# AnalogOutLevelShifter.net
KiCad netlist of a schematic drawn in Altium Designer
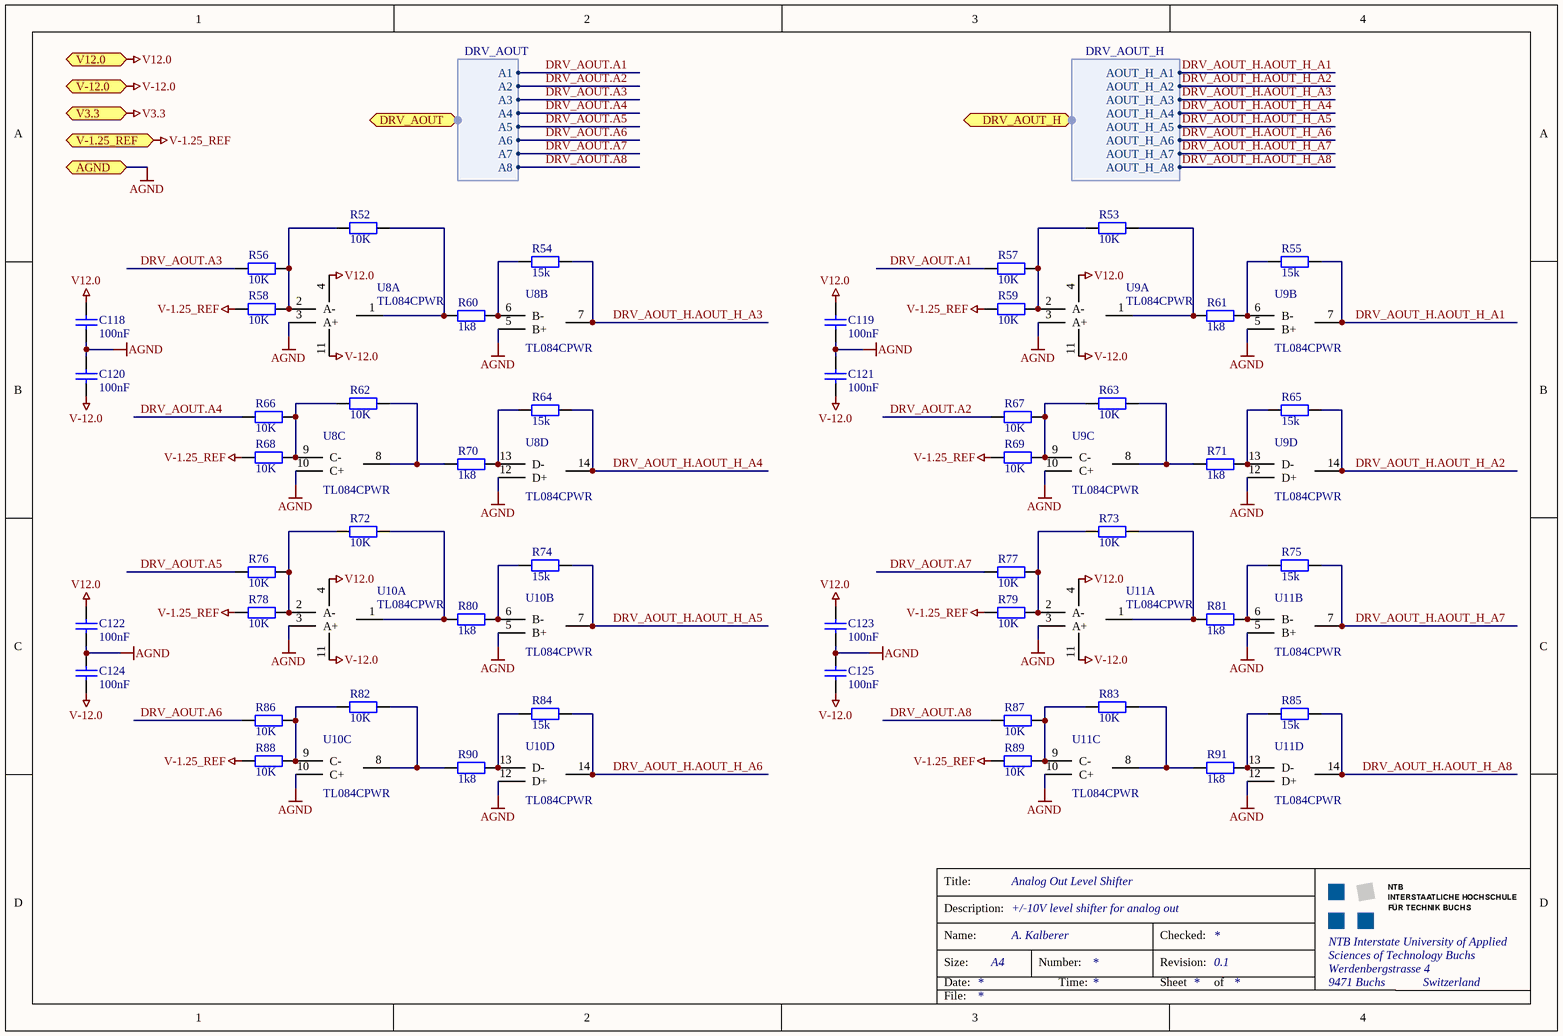
[diagram p0: AnalogOutLevelShifter.SchDoc]

(export (version "E")
  (design (tool "Eeschema 10.0.6"))
  (components
    (comp (ref "C118")
      (value "100nF")
      (footprint "0603_3D")
      (description "Capacitor")
      (fields (field (name "#PUBLISHER") "Dr. A. Heinzelmann"))
      (libsource (lib "ELE-LIB") (part "C"))
    )
    (comp (ref "C119")
      (value "100nF")
      (footprint "0603_3D")
      (description "Capacitor")
      (fields (field (name "#PUBLISHER") "Dr. A. Heinzelmann"))
      (libsource (lib "ELE-LIB") (part "C"))
    )
    (comp (ref "C120")
      (value "100nF")
      (footprint "0603_3D")
      (description "Capacitor")
      (fields (field (name "#PUBLISHER") "Dr. A. Heinzelmann"))
      (libsource (lib "ELE-LIB") (part "C"))
    )
    (comp (ref "C121")
      (value "100nF")
      (footprint "0603_3D")
      (description "Capacitor")
      (fields (field (name "#PUBLISHER") "Dr. A. Heinzelmann"))
      (libsource (lib "ELE-LIB") (part "C"))
    )
    (comp (ref "C122")
      (value "100nF")
      (footprint "0603_3D")
      (description "Capacitor")
      (fields (field (name "#PUBLISHER") "Dr. A. Heinzelmann"))
      (libsource (lib "ELE-LIB") (part "C"))
    )
    (comp (ref "C123")
      (value "100nF")
      (footprint "0603_3D")
      (description "Capacitor")
      (fields (field (name "#PUBLISHER") "Dr. A. Heinzelmann"))
      (libsource (lib "ELE-LIB") (part "C"))
    )
    (comp (ref "C124")
      (value "100nF")
      (footprint "0603_3D")
      (description "Capacitor")
      (fields (field (name "#PUBLISHER") "Dr. A. Heinzelmann"))
      (libsource (lib "ELE-LIB") (part "C"))
    )
    (comp (ref "C125")
      (value "100nF")
      (footprint "0603_3D")
      (description "Capacitor")
      (fields (field (name "#PUBLISHER") "Dr. A. Heinzelmann"))
      (libsource (lib "ELE-LIB") (part "C"))
    )
    (comp (ref "R52")
      (value "10K")
      (footprint "0603_3D")
      (description "Resistor")
      (fields (field (name "#PUBLISHER") "Dr. A. Heinzelmann"))
      (libsource (lib "PartLib") (part "R"))
    )
    (comp (ref "R53")
      (value "10K")
      (footprint "0603_3D")
      (description "Resistor")
      (fields (field (name "#PUBLISHER") "Dr. A. Heinzelmann"))
      (libsource (lib "PartLib") (part "R"))
    )
    (comp (ref "R54")
      (value "15k")
      (footprint "0603_3D")
      (description "Resistor")
      (fields (field (name "#PUBLISHER") "Dr. A. Heinzelmann"))
      (libsource (lib "PartLib") (part "R"))
    )
    (comp (ref "R55")
      (value "15k")
      (footprint "0603_3D")
      (description "Resistor")
      (fields (field (name "#PUBLISHER") "Dr. A. Heinzelmann"))
      (libsource (lib "PartLib") (part "R"))
    )
    (comp (ref "R56")
      (value "10K")
      (footprint "0603_3D")
      (description "Resistor")
      (fields (field (name "#PUBLISHER") "Dr. A. Heinzelmann"))
      (libsource (lib "PartLib") (part "R"))
    )
    (comp (ref "R57")
      (value "10K")
      (footprint "0603_3D")
      (description "Resistor")
      (fields (field (name "#PUBLISHER") "Dr. A. Heinzelmann"))
      (libsource (lib "PartLib") (part "R"))
    )
    (comp (ref "R58")
      (value "10K")
      (footprint "0603_3D")
      (description "Resistor")
      (fields (field (name "#PUBLISHER") "Dr. A. Heinzelmann"))
      (libsource (lib "PartLib") (part "R"))
    )
    (comp (ref "R59")
      (value "10K")
      (footprint "0603_3D")
      (description "Resistor")
      (fields (field (name "#PUBLISHER") "Dr. A. Heinzelmann"))
      (libsource (lib "PartLib") (part "R"))
    )
    (comp (ref "R60")
      (value "1k8")
      (footprint "0603_3D")
      (description "Resistor")
      (fields (field (name "#PUBLISHER") "Dr. A. Heinzelmann"))
      (libsource (lib "PartLib") (part "R"))
    )
    (comp (ref "R61")
      (value "1k8")
      (footprint "0603_3D")
      (description "Resistor")
      (fields (field (name "#PUBLISHER") "Dr. A. Heinzelmann"))
      (libsource (lib "PartLib") (part "R"))
    )
    (comp (ref "R62")
      (value "10K")
      (footprint "0603_3D")
      (description "Resistor")
      (fields (field (name "#PUBLISHER") "Dr. A. Heinzelmann"))
      (libsource (lib "PartLib") (part "R"))
    )
    (comp (ref "R63")
      (value "10K")
      (footprint "0603_3D")
      (description "Resistor")
      (fields (field (name "#PUBLISHER") "Dr. A. Heinzelmann"))
      (libsource (lib "PartLib") (part "R"))
    )
    (comp (ref "R64")
      (value "15k")
      (footprint "0603_3D")
      (description "Resistor")
      (fields (field (name "#PUBLISHER") "Dr. A. Heinzelmann"))
      (libsource (lib "PartLib") (part "R"))
    )
    (comp (ref "R65")
      (value "15k")
      (footprint "0603_3D")
      (description "Resistor")
      (fields (field (name "#PUBLISHER") "Dr. A. Heinzelmann"))
      (libsource (lib "PartLib") (part "R"))
    )
    (comp (ref "R66")
      (value "10K")
      (footprint "0603_3D")
      (description "Resistor")
      (fields (field (name "#PUBLISHER") "Dr. A. Heinzelmann"))
      (libsource (lib "PartLib") (part "R"))
    )
    (comp (ref "R67")
      (value "10K")
      (footprint "0603_3D")
      (description "Resistor")
      (fields (field (name "#PUBLISHER") "Dr. A. Heinzelmann"))
      (libsource (lib "PartLib") (part "R"))
    )
    (comp (ref "R68")
      (value "10K")
      (footprint "0603_3D")
      (description "Resistor")
      (fields (field (name "#PUBLISHER") "Dr. A. Heinzelmann"))
      (libsource (lib "PartLib") (part "R"))
    )
    (comp (ref "R69")
      (value "10K")
      (footprint "0603_3D")
      (description "Resistor")
      (fields (field (name "#PUBLISHER") "Dr. A. Heinzelmann"))
      (libsource (lib "PartLib") (part "R"))
    )
    (comp (ref "R70")
      (value "1k8")
      (footprint "0603_3D")
      (description "Resistor")
      (fields (field (name "#PUBLISHER") "Dr. A. Heinzelmann"))
      (libsource (lib "PartLib") (part "R"))
    )
    (comp (ref "R71")
      (value "1k8")
      (footprint "0603_3D")
      (description "Resistor")
      (fields (field (name "#PUBLISHER") "Dr. A. Heinzelmann"))
      (libsource (lib "PartLib") (part "R"))
    )
    (comp (ref "R72")
      (value "10K")
      (footprint "0603_3D")
      (description "Resistor")
      (fields (field (name "#PUBLISHER") "Dr. A. Heinzelmann"))
      (libsource (lib "PartLib") (part "R"))
    )
    (comp (ref "R73")
      (value "10K")
      (footprint "0603_3D")
      (description "Resistor")
      (fields (field (name "#PUBLISHER") "Dr. A. Heinzelmann"))
      (libsource (lib "PartLib") (part "R"))
    )
    (comp (ref "R74")
      (value "15k")
      (footprint "0603_3D")
      (description "Resistor")
      (fields (field (name "#PUBLISHER") "Dr. A. Heinzelmann"))
      (libsource (lib "PartLib") (part "R"))
    )
    (comp (ref "R75")
      (value "15k")
      (footprint "0603_3D")
      (description "Resistor")
      (fields (field (name "#PUBLISHER") "Dr. A. Heinzelmann"))
      (libsource (lib "PartLib") (part "R"))
    )
    (comp (ref "R76")
      (value "10K")
      (footprint "0603_3D")
      (description "Resistor")
      (fields (field (name "#PUBLISHER") "Dr. A. Heinzelmann"))
      (libsource (lib "PartLib") (part "R"))
    )
    (comp (ref "R77")
      (value "10K")
      (footprint "0603_3D")
      (description "Resistor")
      (fields (field (name "#PUBLISHER") "Dr. A. Heinzelmann"))
      (libsource (lib "PartLib") (part "R"))
    )
    (comp (ref "R78")
      (value "10K")
      (footprint "0603_3D")
      (description "Resistor")
      (fields (field (name "#PUBLISHER") "Dr. A. Heinzelmann"))
      (libsource (lib "PartLib") (part "R"))
    )
    (comp (ref "R79")
      (value "10K")
      (footprint "0603_3D")
      (description "Resistor")
      (fields (field (name "#PUBLISHER") "Dr. A. Heinzelmann"))
      (libsource (lib "PartLib") (part "R"))
    )
    (comp (ref "R80")
      (value "1k8")
      (footprint "0603_3D")
      (description "Resistor")
      (fields (field (name "#PUBLISHER") "Dr. A. Heinzelmann"))
      (libsource (lib "PartLib") (part "R"))
    )
    (comp (ref "R81")
      (value "1k8")
      (footprint "0603_3D")
      (description "Resistor")
      (fields (field (name "#PUBLISHER") "Dr. A. Heinzelmann"))
      (libsource (lib "PartLib") (part "R"))
    )
    (comp (ref "R82")
      (value "10K")
      (footprint "0603_3D")
      (description "Resistor")
      (fields (field (name "#PUBLISHER") "Dr. A. Heinzelmann"))
      (libsource (lib "PartLib") (part "R"))
    )
    (comp (ref "R83")
      (value "10K")
      (footprint "0603_3D")
      (description "Resistor")
      (fields (field (name "#PUBLISHER") "Dr. A. Heinzelmann"))
      (libsource (lib "PartLib") (part "R"))
    )
    (comp (ref "R84")
      (value "15k")
      (footprint "0603_3D")
      (description "Resistor")
      (fields (field (name "#PUBLISHER") "Dr. A. Heinzelmann"))
      (libsource (lib "PartLib") (part "R"))
    )
    (comp (ref "R85")
      (value "15k")
      (footprint "0603_3D")
      (description "Resistor")
      (fields (field (name "#PUBLISHER") "Dr. A. Heinzelmann"))
      (libsource (lib "PartLib") (part "R"))
    )
    (comp (ref "R86")
      (value "10K")
      (footprint "0603_3D")
      (description "Resistor")
      (fields (field (name "#PUBLISHER") "Dr. A. Heinzelmann"))
      (libsource (lib "PartLib") (part "R"))
    )
    (comp (ref "R87")
      (value "10K")
      (footprint "0603_3D")
      (description "Resistor")
      (fields (field (name "#PUBLISHER") "Dr. A. Heinzelmann"))
      (libsource (lib "PartLib") (part "R"))
    )
    (comp (ref "R88")
      (value "10K")
      (footprint "0603_3D")
      (description "Resistor")
      (fields (field (name "#PUBLISHER") "Dr. A. Heinzelmann"))
      (libsource (lib "PartLib") (part "R"))
    )
    (comp (ref "R89")
      (value "10K")
      (footprint "0603_3D")
      (description "Resistor")
      (fields (field (name "#PUBLISHER") "Dr. A. Heinzelmann"))
      (libsource (lib "PartLib") (part "R"))
    )
    (comp (ref "R90")
      (value "1k8")
      (footprint "0603_3D")
      (description "Resistor")
      (fields (field (name "#PUBLISHER") "Dr. A. Heinzelmann"))
      (libsource (lib "PartLib") (part "R"))
    )
    (comp (ref "R91")
      (value "1k8")
      (footprint "0603_3D")
      (description "Resistor")
      (fields (field (name "#PUBLISHER") "Dr. A. Heinzelmann"))
      (libsource (lib "PartLib") (part "R"))
    )
    (comp (ref "U8")
      (value "TL084CPWR")
      (footprint "TSOP65P640X120-14N")
      (description "Quad OPAmp")
      (libsource (lib "PartLib") (part "TL084CPWR"))
    )
    (comp (ref "U9")
      (value "TL084CPWR")
      (footprint "TSOP65P640X120-14N")
      (description "Quad OPAmp")
      (libsource (lib "PartLib") (part "TL084CPWR"))
    )
    (comp (ref "U10")
      (value "TL084CPWR")
      (footprint "TSOP65P640X120-14N")
      (description "Quad OPAmp")
      (libsource (lib "PartLib") (part "TL084CPWR"))
    )
    (comp (ref "U11")
      (value "TL084CPWR")
      (footprint "TSOP65P640X120-14N")
      (description "Quad OPAmp")
      (libsource (lib "PartLib") (part "TL084CPWR"))
    )
  )
  (nets
    (net (code "3") (name "/DRV_AOUT.A1") (class "Default")
      (node (ref "R57") (pin "1") (pinfunction "1_1") (pintype "passive"))
    )
    (net (code "4") (name "/DRV_AOUT.A2") (class "Default")
      (node (ref "R67") (pin "1") (pinfunction "1_1") (pintype "passive"))
    )
    (net (code "5") (name "/DRV_AOUT.A3") (class "Default")
      (node (ref "R56") (pin "1") (pinfunction "1_1") (pintype "passive"))
    )
    (net (code "6") (name "/DRV_AOUT.A4") (class "Default")
      (node (ref "R66") (pin "1") (pinfunction "1_1") (pintype "passive"))
    )
    (net (code "7") (name "/DRV_AOUT.A5") (class "Default")
      (node (ref "R76") (pin "1") (pinfunction "1_1") (pintype "passive"))
    )
    (net (code "8") (name "/DRV_AOUT.A6") (class "Default")
      (node (ref "R86") (pin "1") (pinfunction "1_1") (pintype "passive"))
    )
    (net (code "9") (name "/DRV_AOUT.A7") (class "Default")
      (node (ref "R77") (pin "1") (pinfunction "1_1") (pintype "passive"))
    )
    (net (code "10") (name "/DRV_AOUT.A8") (class "Default")
      (node (ref "R87") (pin "1") (pinfunction "1_1") (pintype "passive"))
    )
    (net (code "11") (name "/DRV_AOUT_H.AOUT_H_A1") (class "Default")
      (node (ref "R55") (pin "2") (pinfunction "2_2") (pintype "passive"))
      (node (ref "U9") (pin "7") (pinfunction "Bout_7") (pintype "passive"))
    )
    (net (code "12") (name "/DRV_AOUT_H.AOUT_H_A2") (class "Default")
      (node (ref "R65") (pin "2") (pinfunction "2_2") (pintype "passive"))
      (node (ref "U9") (pin "14") (pinfunction "Dout_14") (pintype "passive"))
    )
    (net (code "13") (name "/DRV_AOUT_H.AOUT_H_A3") (class "Default")
      (node (ref "R54") (pin "2") (pinfunction "2_2") (pintype "passive"))
      (node (ref "U8") (pin "7") (pinfunction "Bout_7") (pintype "passive"))
    )
    (net (code "14") (name "/DRV_AOUT_H.AOUT_H_A4") (class "Default")
      (node (ref "R64") (pin "2") (pinfunction "2_2") (pintype "passive"))
      (node (ref "U8") (pin "14") (pinfunction "Dout_14") (pintype "passive"))
    )
    (net (code "15") (name "/DRV_AOUT_H.AOUT_H_A5") (class "Default")
      (node (ref "R74") (pin "2") (pinfunction "2_2") (pintype "passive"))
      (node (ref "U10") (pin "7") (pinfunction "Bout_7") (pintype "passive"))
    )
    (net (code "16") (name "/DRV_AOUT_H.AOUT_H_A6") (class "Default")
      (node (ref "R84") (pin "2") (pinfunction "2_2") (pintype "passive"))
      (node (ref "U10") (pin "14") (pinfunction "Dout_14") (pintype "passive"))
    )
    (net (code "17") (name "/DRV_AOUT_H.AOUT_H_A7") (class "Default")
      (node (ref "R75") (pin "2") (pinfunction "2_2") (pintype "passive"))
      (node (ref "U11") (pin "7") (pinfunction "Bout_7") (pintype "passive"))
    )
    (net (code "18") (name "/DRV_AOUT_H.AOUT_H_A8") (class "Default")
      (node (ref "R85") (pin "2") (pinfunction "2_2") (pintype "passive"))
      (node (ref "U11") (pin "14") (pinfunction "Dout_14") (pintype "passive"))
    )
    (net (code "21") (name "AGND") (class "Default")
      (node (ref "C118") (pin "1") (pinfunction "1_1") (pintype "passive"))
      (node (ref "C119") (pin "1") (pinfunction "1_1") (pintype "passive"))
      (node (ref "C120") (pin "2") (pinfunction "2_2") (pintype "passive"))
      (node (ref "C121") (pin "2") (pinfunction "2_2") (pintype "passive"))
      (node (ref "C122") (pin "1") (pinfunction "1_1") (pintype "passive"))
      (node (ref "C123") (pin "1") (pinfunction "1_1") (pintype "passive"))
      (node (ref "C124") (pin "2") (pinfunction "2_2") (pintype "passive"))
      (node (ref "C125") (pin "2") (pinfunction "2_2") (pintype "passive"))
      (node (ref "U10") (pin "10") (pinfunction "C+_10") (pintype "passive"))
      (node (ref "U10") (pin "12") (pinfunction "D+_12") (pintype "passive"))
      (node (ref "U10") (pin "3") (pinfunction "A+_3") (pintype "passive"))
      (node (ref "U10") (pin "5") (pinfunction "B+_5") (pintype "passive"))
      (node (ref "U11") (pin "10") (pinfunction "C+_10") (pintype "passive"))
      (node (ref "U11") (pin "12") (pinfunction "D+_12") (pintype "passive"))
      (node (ref "U11") (pin "3") (pinfunction "A+_3") (pintype "passive"))
      (node (ref "U11") (pin "5") (pinfunction "B+_5") (pintype "passive"))
      (node (ref "U8") (pin "10") (pinfunction "C+_10") (pintype "passive"))
      (node (ref "U8") (pin "12") (pinfunction "D+_12") (pintype "passive"))
      (node (ref "U8") (pin "3") (pinfunction "A+_3") (pintype "passive"))
      (node (ref "U8") (pin "5") (pinfunction "B+_5") (pintype "passive"))
      (node (ref "U9") (pin "10") (pinfunction "C+_10") (pintype "passive"))
      (node (ref "U9") (pin "12") (pinfunction "D+_12") (pintype "passive"))
      (node (ref "U9") (pin "3") (pinfunction "A+_3") (pintype "passive"))
      (node (ref "U9") (pin "5") (pinfunction "B+_5") (pintype "passive"))
    )
    (net (code "22") (name "Net-(U8A-A-)") (class "Default")
      (node (ref "R52") (pin "1") (pinfunction "1_1") (pintype "passive"))
      (node (ref "R56") (pin "2") (pinfunction "2_2") (pintype "passive"))
      (node (ref "R58") (pin "2") (pinfunction "2_2") (pintype "passive"))
      (node (ref "U8") (pin "2") (pinfunction "A-_2") (pintype "passive"))
    )
    (net (code "23") (name "Net-(U8A-Aout)") (class "Default")
      (node (ref "R52") (pin "2") (pinfunction "2_2") (pintype "passive"))
      (node (ref "R60") (pin "1") (pinfunction "1_1") (pintype "passive"))
      (node (ref "U8") (pin "1") (pinfunction "Aout_1") (pintype "passive"))
    )
    (net (code "24") (name "Net-(U8B-B-)") (class "Default")
      (node (ref "R54") (pin "1") (pinfunction "1_1") (pintype "passive"))
      (node (ref "R60") (pin "2") (pinfunction "2_2") (pintype "passive"))
      (node (ref "U8") (pin "6") (pinfunction "B-_6") (pintype "passive"))
    )
    (net (code "25") (name "Net-(U8C-C-)") (class "Default")
      (node (ref "R62") (pin "1") (pinfunction "1_1") (pintype "passive"))
      (node (ref "R66") (pin "2") (pinfunction "2_2") (pintype "passive"))
      (node (ref "R68") (pin "2") (pinfunction "2_2") (pintype "passive"))
      (node (ref "U8") (pin "9") (pinfunction "C-_9") (pintype "passive"))
    )
    (net (code "26") (name "Net-(U8C-Cout)") (class "Default")
      (node (ref "R62") (pin "2") (pinfunction "2_2") (pintype "passive"))
      (node (ref "R70") (pin "1") (pinfunction "1_1") (pintype "passive"))
      (node (ref "U8") (pin "8") (pinfunction "Cout_8") (pintype "passive"))
    )
    (net (code "27") (name "Net-(U8D-D-)") (class "Default")
      (node (ref "R64") (pin "1") (pinfunction "1_1") (pintype "passive"))
      (node (ref "R70") (pin "2") (pinfunction "2_2") (pintype "passive"))
      (node (ref "U8") (pin "13") (pinfunction "D-_13") (pintype "passive"))
    )
    (net (code "28") (name "Net-(U9A-A-)") (class "Default")
      (node (ref "R53") (pin "1") (pinfunction "1_1") (pintype "passive"))
      (node (ref "R57") (pin "2") (pinfunction "2_2") (pintype "passive"))
      (node (ref "R59") (pin "2") (pinfunction "2_2") (pintype "passive"))
      (node (ref "U9") (pin "2") (pinfunction "A-_2") (pintype "passive"))
    )
    (net (code "29") (name "Net-(U9A-Aout)") (class "Default")
      (node (ref "R53") (pin "2") (pinfunction "2_2") (pintype "passive"))
      (node (ref "R61") (pin "1") (pinfunction "1_1") (pintype "passive"))
      (node (ref "U9") (pin "1") (pinfunction "Aout_1") (pintype "passive"))
    )
    (net (code "30") (name "Net-(U9B-B-)") (class "Default")
      (node (ref "R55") (pin "1") (pinfunction "1_1") (pintype "passive"))
      (node (ref "R61") (pin "2") (pinfunction "2_2") (pintype "passive"))
      (node (ref "U9") (pin "6") (pinfunction "B-_6") (pintype "passive"))
    )
    (net (code "31") (name "Net-(U9C-C-)") (class "Default")
      (node (ref "R63") (pin "1") (pinfunction "1_1") (pintype "passive"))
      (node (ref "R67") (pin "2") (pinfunction "2_2") (pintype "passive"))
      (node (ref "R69") (pin "2") (pinfunction "2_2") (pintype "passive"))
      (node (ref "U9") (pin "9") (pinfunction "C-_9") (pintype "passive"))
    )
    (net (code "32") (name "Net-(U9C-Cout)") (class "Default")
      (node (ref "R63") (pin "2") (pinfunction "2_2") (pintype "passive"))
      (node (ref "R71") (pin "1") (pinfunction "1_1") (pintype "passive"))
      (node (ref "U9") (pin "8") (pinfunction "Cout_8") (pintype "passive"))
    )
    (net (code "33") (name "Net-(U9D-D-)") (class "Default")
      (node (ref "R65") (pin "1") (pinfunction "1_1") (pintype "passive"))
      (node (ref "R71") (pin "2") (pinfunction "2_2") (pintype "passive"))
      (node (ref "U9") (pin "13") (pinfunction "D-_13") (pintype "passive"))
    )
    (net (code "34") (name "Net-(U10A-A-)") (class "Default")
      (node (ref "R72") (pin "1") (pinfunction "1_1") (pintype "passive"))
      (node (ref "R76") (pin "2") (pinfunction "2_2") (pintype "passive"))
      (node (ref "R78") (pin "2") (pinfunction "2_2") (pintype "passive"))
      (node (ref "U10") (pin "2") (pinfunction "A-_2") (pintype "passive"))
    )
    (net (code "35") (name "Net-(U10A-Aout)") (class "Default")
      (node (ref "R72") (pin "2") (pinfunction "2_2") (pintype "passive"))
      (node (ref "R80") (pin "1") (pinfunction "1_1") (pintype "passive"))
      (node (ref "U10") (pin "1") (pinfunction "Aout_1") (pintype "passive"))
    )
    (net (code "36") (name "Net-(U10B-B-)") (class "Default")
      (node (ref "R74") (pin "1") (pinfunction "1_1") (pintype "passive"))
      (node (ref "R80") (pin "2") (pinfunction "2_2") (pintype "passive"))
      (node (ref "U10") (pin "6") (pinfunction "B-_6") (pintype "passive"))
    )
    (net (code "37") (name "Net-(U10C-C-)") (class "Default")
      (node (ref "R82") (pin "1") (pinfunction "1_1") (pintype "passive"))
      (node (ref "R86") (pin "2") (pinfunction "2_2") (pintype "passive"))
      (node (ref "R88") (pin "2") (pinfunction "2_2") (pintype "passive"))
      (node (ref "U10") (pin "9") (pinfunction "C-_9") (pintype "passive"))
    )
    (net (code "38") (name "Net-(U10C-Cout)") (class "Default")
      (node (ref "R82") (pin "2") (pinfunction "2_2") (pintype "passive"))
      (node (ref "R90") (pin "1") (pinfunction "1_1") (pintype "passive"))
      (node (ref "U10") (pin "8") (pinfunction "Cout_8") (pintype "passive"))
    )
    (net (code "39") (name "Net-(U10D-D-)") (class "Default")
      (node (ref "R84") (pin "1") (pinfunction "1_1") (pintype "passive"))
      (node (ref "R90") (pin "2") (pinfunction "2_2") (pintype "passive"))
      (node (ref "U10") (pin "13") (pinfunction "D-_13") (pintype "passive"))
    )
    (net (code "40") (name "Net-(U11A-A-)") (class "Default")
      (node (ref "R73") (pin "1") (pinfunction "1_1") (pintype "passive"))
      (node (ref "R77") (pin "2") (pinfunction "2_2") (pintype "passive"))
      (node (ref "R79") (pin "2") (pinfunction "2_2") (pintype "passive"))
      (node (ref "U11") (pin "2") (pinfunction "A-_2") (pintype "passive"))
    )
    (net (code "41") (name "Net-(U11A-Aout)") (class "Default")
      (node (ref "R73") (pin "2") (pinfunction "2_2") (pintype "passive"))
      (node (ref "R81") (pin "1") (pinfunction "1_1") (pintype "passive"))
      (node (ref "U11") (pin "1") (pinfunction "Aout_1") (pintype "passive"))
    )
    (net (code "42") (name "Net-(U11B-B-)") (class "Default")
      (node (ref "R75") (pin "1") (pinfunction "1_1") (pintype "passive"))
      (node (ref "R81") (pin "2") (pinfunction "2_2") (pintype "passive"))
      (node (ref "U11") (pin "6") (pinfunction "B-_6") (pintype "passive"))
    )
    (net (code "43") (name "Net-(U11C-C-)") (class "Default")
      (node (ref "R83") (pin "1") (pinfunction "1_1") (pintype "passive"))
      (node (ref "R87") (pin "2") (pinfunction "2_2") (pintype "passive"))
      (node (ref "R89") (pin "2") (pinfunction "2_2") (pintype "passive"))
      (node (ref "U11") (pin "9") (pinfunction "C-_9") (pintype "passive"))
    )
    (net (code "44") (name "Net-(U11C-Cout)") (class "Default")
      (node (ref "R83") (pin "2") (pinfunction "2_2") (pintype "passive"))
      (node (ref "R91") (pin "1") (pinfunction "1_1") (pintype "passive"))
      (node (ref "U11") (pin "8") (pinfunction "Cout_8") (pintype "passive"))
    )
    (net (code "45") (name "Net-(U11D-D-)") (class "Default")
      (node (ref "R85") (pin "1") (pinfunction "1_1") (pintype "passive"))
      (node (ref "R91") (pin "2") (pinfunction "2_2") (pintype "passive"))
      (node (ref "U11") (pin "13") (pinfunction "D-_13") (pintype "passive"))
    )
    (net (code "46") (name "V-1.25_REF") (class "Default")
      (node (ref "R58") (pin "1") (pinfunction "1_1") (pintype "passive"))
      (node (ref "R59") (pin "1") (pinfunction "1_1") (pintype "passive"))
      (node (ref "R68") (pin "1") (pinfunction "1_1") (pintype "passive"))
      (node (ref "R69") (pin "1") (pinfunction "1_1") (pintype "passive"))
      (node (ref "R78") (pin "1") (pinfunction "1_1") (pintype "passive"))
      (node (ref "R79") (pin "1") (pinfunction "1_1") (pintype "passive"))
      (node (ref "R88") (pin "1") (pinfunction "1_1") (pintype "passive"))
      (node (ref "R89") (pin "1") (pinfunction "1_1") (pintype "passive"))
    )
    (net (code "47") (name "V-12.0") (class "Default")
      (node (ref "C120") (pin "1") (pinfunction "1_1") (pintype "passive"))
      (node (ref "C121") (pin "1") (pinfunction "1_1") (pintype "passive"))
      (node (ref "C124") (pin "1") (pinfunction "1_1") (pintype "passive"))
      (node (ref "C125") (pin "1") (pinfunction "1_1") (pintype "passive"))
      (node (ref "U10") (pin "11") (pinfunction "V-_11") (pintype "passive"))
      (node (ref "U11") (pin "11") (pinfunction "V-_11") (pintype "passive"))
      (node (ref "U8") (pin "11") (pinfunction "V-_11") (pintype "passive"))
      (node (ref "U9") (pin "11") (pinfunction "V-_11") (pintype "passive"))
    )
    (net (code "49") (name "V12.0") (class "Default")
      (node (ref "C118") (pin "2") (pinfunction "2_2") (pintype "passive"))
      (node (ref "C119") (pin "2") (pinfunction "2_2") (pintype "passive"))
      (node (ref "C122") (pin "2") (pinfunction "2_2") (pintype "passive"))
      (node (ref "C123") (pin "2") (pinfunction "2_2") (pintype "passive"))
      (node (ref "U10") (pin "4") (pinfunction "V+_4") (pintype "passive"))
      (node (ref "U11") (pin "4") (pinfunction "V+_4") (pintype "passive"))
      (node (ref "U8") (pin "4") (pinfunction "V+_4") (pintype "passive"))
      (node (ref "U9") (pin "4") (pinfunction "V+_4") (pintype "passive"))
    )
  )
)
